# ledstripes.net
KiCad netlist of a schematic drawn in Altium Designer
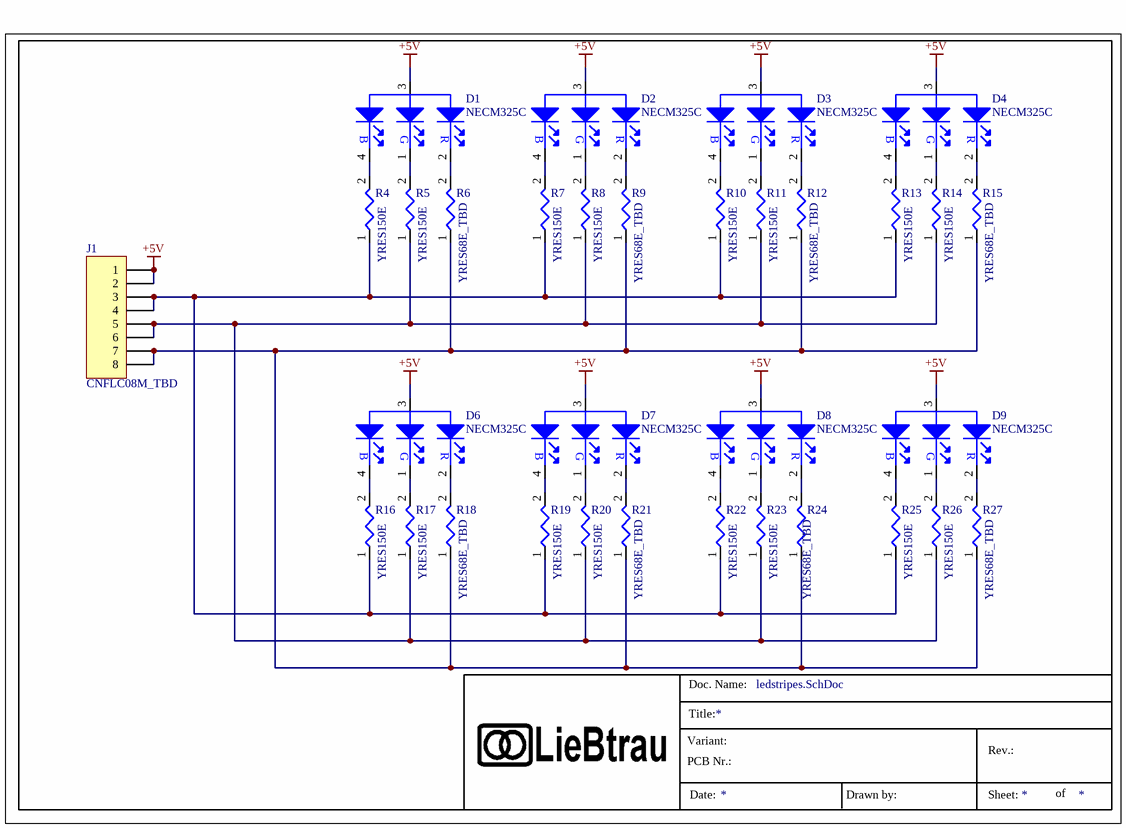
[diagram p0: ledstripes.SchDoc]

(export (version "E")
  (design (tool "Eeschema 10.0.6"))
  (components
    (comp (ref "D1")
      (value "NECM325C")
      (footprint "D_NECM325C")
      (libsource (lib "Testing") (part "D_LED_RGB"))
    )
    (comp (ref "D2")
      (value "NECM325C")
      (footprint "D_NECM325C")
      (libsource (lib "Testing") (part "D_LED_RGB"))
    )
    (comp (ref "D3")
      (value "NECM325C")
      (footprint "D_NECM325C")
      (libsource (lib "Testing") (part "D_LED_RGB"))
    )
    (comp (ref "D4")
      (value "NECM325C")
      (footprint "D_NECM325C")
      (libsource (lib "Testing") (part "D_LED_RGB"))
    )
    (comp (ref "D6")
      (value "NECM325C")
      (footprint "D_NECM325C")
      (libsource (lib "Testing") (part "D_LED_RGB"))
    )
    (comp (ref "D7")
      (value "NECM325C")
      (footprint "D_NECM325C")
      (libsource (lib "Testing") (part "D_LED_RGB"))
    )
    (comp (ref "D8")
      (value "NECM325C")
      (footprint "D_NECM325C")
      (libsource (lib "Testing") (part "D_LED_RGB"))
    )
    (comp (ref "D9")
      (value "NECM325C")
      (footprint "D_NECM325C")
      (libsource (lib "Testing") (part "D_LED_RGB"))
    )
    (comp (ref "J1")
      (value "CNFLC08M_TBD")
      (footprint "J_215079-8")
      (fields (field (name "PART NUMBER") "CNFLC08F_TBD"))
      (libsource (lib "Testing") (part "J_8P"))
    )
    (comp (ref "R4")
      (value "YRES150E")
      (footprint "R_1206")
      (description "Resistor")
      (libsource (lib "Testing") (part "R_RES"))
    )
    (comp (ref "R5")
      (value "YRES150E")
      (footprint "R_1206")
      (description "Resistor")
      (libsource (lib "Testing") (part "R_RES"))
    )
    (comp (ref "R6")
      (value "YRES68E_TBD")
      (footprint "R_1206")
      (description "Resistor")
      (libsource (lib "Testing") (part "R_RES"))
    )
    (comp (ref "R7")
      (value "YRES150E")
      (footprint "R_1206")
      (description "Resistor")
      (libsource (lib "Testing") (part "R_RES"))
    )
    (comp (ref "R8")
      (value "YRES150E")
      (footprint "R_1206")
      (description "Resistor")
      (libsource (lib "Testing") (part "R_RES"))
    )
    (comp (ref "R9")
      (value "YRES68E_TBD")
      (footprint "R_1206")
      (description "Resistor")
      (libsource (lib "Testing") (part "R_RES"))
    )
    (comp (ref "R10")
      (value "YRES150E")
      (footprint "R_1206")
      (description "Resistor")
      (libsource (lib "Testing") (part "R_RES"))
    )
    (comp (ref "R11")
      (value "YRES150E")
      (footprint "R_1206")
      (description "Resistor")
      (libsource (lib "Testing") (part "R_RES"))
    )
    (comp (ref "R12")
      (value "YRES68E_TBD")
      (footprint "R_1206")
      (description "Resistor")
      (libsource (lib "Testing") (part "R_RES"))
    )
    (comp (ref "R13")
      (value "YRES150E")
      (footprint "R_1206")
      (description "Resistor")
      (libsource (lib "Testing") (part "R_RES"))
    )
    (comp (ref "R14")
      (value "YRES150E")
      (footprint "R_1206")
      (description "Resistor")
      (libsource (lib "Testing") (part "R_RES"))
    )
    (comp (ref "R15")
      (value "YRES68E_TBD")
      (footprint "R_1206")
      (description "Resistor")
      (libsource (lib "Testing") (part "R_RES"))
    )
    (comp (ref "R16")
      (value "YRES150E")
      (footprint "R_1206")
      (description "Resistor")
      (libsource (lib "Testing") (part "R_RES"))
    )
    (comp (ref "R17")
      (value "YRES150E")
      (footprint "R_1206")
      (description "Resistor")
      (libsource (lib "Testing") (part "R_RES"))
    )
    (comp (ref "R18")
      (value "YRES68E_TBD")
      (footprint "R_1206")
      (description "Resistor")
      (libsource (lib "Testing") (part "R_RES"))
    )
    (comp (ref "R19")
      (value "YRES150E")
      (footprint "R_1206")
      (description "Resistor")
      (libsource (lib "Testing") (part "R_RES"))
    )
    (comp (ref "R20")
      (value "YRES150E")
      (footprint "R_1206")
      (description "Resistor")
      (libsource (lib "Testing") (part "R_RES"))
    )
    (comp (ref "R21")
      (value "YRES68E_TBD")
      (footprint "R_1206")
      (description "Resistor")
      (libsource (lib "Testing") (part "R_RES"))
    )
    (comp (ref "R22")
      (value "YRES150E")
      (footprint "R_1206")
      (description "Resistor")
      (libsource (lib "Testing") (part "R_RES"))
    )
    (comp (ref "R23")
      (value "YRES150E")
      (footprint "R_1206")
      (description "Resistor")
      (libsource (lib "Testing") (part "R_RES"))
    )
    (comp (ref "R24")
      (value "YRES68E_TBD")
      (footprint "R_1206")
      (description "Resistor")
      (libsource (lib "Testing") (part "R_RES"))
    )
    (comp (ref "R25")
      (value "YRES150E")
      (footprint "R_1206")
      (description "Resistor")
      (libsource (lib "Testing") (part "R_RES"))
    )
    (comp (ref "R26")
      (value "YRES150E")
      (footprint "R_1206")
      (description "Resistor")
      (libsource (lib "Testing") (part "R_RES"))
    )
    (comp (ref "R27")
      (value "YRES68E_TBD")
      (footprint "R_1206")
      (description "Resistor")
      (libsource (lib "Testing") (part "R_RES"))
    )
  )
  (nets
    (net (code "1") (name "+5V") (class "Default")
      (node (ref "D1") (pin "3") (pinfunction "A_3") (pintype "passive"))
      (node (ref "D2") (pin "3") (pinfunction "A_3") (pintype "passive"))
      (node (ref "D3") (pin "3") (pinfunction "A_3") (pintype "passive"))
      (node (ref "D4") (pin "3") (pinfunction "A_3") (pintype "passive"))
      (node (ref "D6") (pin "3") (pinfunction "A_3") (pintype "passive"))
      (node (ref "D7") (pin "3") (pinfunction "A_3") (pintype "passive"))
      (node (ref "D8") (pin "3") (pinfunction "A_3") (pintype "passive"))
      (node (ref "D9") (pin "3") (pinfunction "A_3") (pintype "passive"))
      (node (ref "J1") (pin "1") (pinfunction "1_1") (pintype "passive"))
      (node (ref "J1") (pin "2") (pinfunction "2_2") (pintype "passive"))
    )
    (net (code "2") (name "Net-(D1-C-Pad1)") (class "Default")
      (node (ref "D1") (pin "1") (pinfunction "C_1") (pintype "passive"))
      (node (ref "R5") (pin "2") (pinfunction "2_2") (pintype "passive"))
    )
    (net (code "3") (name "Net-(D1-C-Pad2)") (class "Default")
      (node (ref "D1") (pin "2") (pinfunction "C_2") (pintype "passive"))
      (node (ref "R6") (pin "2") (pinfunction "2_2") (pintype "passive"))
    )
    (net (code "4") (name "Net-(D1-C-Pad4)") (class "Default")
      (node (ref "D1") (pin "4") (pinfunction "C_4") (pintype "passive"))
      (node (ref "R4") (pin "2") (pinfunction "2_2") (pintype "passive"))
    )
    (net (code "5") (name "Net-(D2-C-Pad1)") (class "Default")
      (node (ref "D2") (pin "1") (pinfunction "C_1") (pintype "passive"))
      (node (ref "R8") (pin "2") (pinfunction "2_2") (pintype "passive"))
    )
    (net (code "6") (name "Net-(D2-C-Pad2)") (class "Default")
      (node (ref "D2") (pin "2") (pinfunction "C_2") (pintype "passive"))
      (node (ref "R9") (pin "2") (pinfunction "2_2") (pintype "passive"))
    )
    (net (code "7") (name "Net-(D2-C-Pad4)") (class "Default")
      (node (ref "D2") (pin "4") (pinfunction "C_4") (pintype "passive"))
      (node (ref "R7") (pin "2") (pinfunction "2_2") (pintype "passive"))
    )
    (net (code "8") (name "Net-(D3-C-Pad1)") (class "Default")
      (node (ref "D3") (pin "1") (pinfunction "C_1") (pintype "passive"))
      (node (ref "R11") (pin "2") (pinfunction "2_2") (pintype "passive"))
    )
    (net (code "9") (name "Net-(D3-C-Pad2)") (class "Default")
      (node (ref "D3") (pin "2") (pinfunction "C_2") (pintype "passive"))
      (node (ref "R12") (pin "2") (pinfunction "2_2") (pintype "passive"))
    )
    (net (code "10") (name "Net-(D3-C-Pad4)") (class "Default")
      (node (ref "D3") (pin "4") (pinfunction "C_4") (pintype "passive"))
      (node (ref "R10") (pin "2") (pinfunction "2_2") (pintype "passive"))
    )
    (net (code "11") (name "Net-(D4-C-Pad1)") (class "Default")
      (node (ref "D4") (pin "1") (pinfunction "C_1") (pintype "passive"))
      (node (ref "R14") (pin "2") (pinfunction "2_2") (pintype "passive"))
    )
    (net (code "12") (name "Net-(D4-C-Pad2)") (class "Default")
      (node (ref "D4") (pin "2") (pinfunction "C_2") (pintype "passive"))
      (node (ref "R15") (pin "2") (pinfunction "2_2") (pintype "passive"))
    )
    (net (code "13") (name "Net-(D4-C-Pad4)") (class "Default")
      (node (ref "D4") (pin "4") (pinfunction "C_4") (pintype "passive"))
      (node (ref "R13") (pin "2") (pinfunction "2_2") (pintype "passive"))
    )
    (net (code "14") (name "Net-(D6-C-Pad1)") (class "Default")
      (node (ref "D6") (pin "1") (pinfunction "C_1") (pintype "passive"))
      (node (ref "R17") (pin "2") (pinfunction "2_2") (pintype "passive"))
    )
    (net (code "15") (name "Net-(D6-C-Pad2)") (class "Default")
      (node (ref "D6") (pin "2") (pinfunction "C_2") (pintype "passive"))
      (node (ref "R18") (pin "2") (pinfunction "2_2") (pintype "passive"))
    )
    (net (code "16") (name "Net-(D6-C-Pad4)") (class "Default")
      (node (ref "D6") (pin "4") (pinfunction "C_4") (pintype "passive"))
      (node (ref "R16") (pin "2") (pinfunction "2_2") (pintype "passive"))
    )
    (net (code "17") (name "Net-(D7-C-Pad1)") (class "Default")
      (node (ref "D7") (pin "1") (pinfunction "C_1") (pintype "passive"))
      (node (ref "R20") (pin "2") (pinfunction "2_2") (pintype "passive"))
    )
    (net (code "18") (name "Net-(D7-C-Pad2)") (class "Default")
      (node (ref "D7") (pin "2") (pinfunction "C_2") (pintype "passive"))
      (node (ref "R21") (pin "2") (pinfunction "2_2") (pintype "passive"))
    )
    (net (code "19") (name "Net-(D7-C-Pad4)") (class "Default")
      (node (ref "D7") (pin "4") (pinfunction "C_4") (pintype "passive"))
      (node (ref "R19") (pin "2") (pinfunction "2_2") (pintype "passive"))
    )
    (net (code "20") (name "Net-(D8-C-Pad1)") (class "Default")
      (node (ref "D8") (pin "1") (pinfunction "C_1") (pintype "passive"))
      (node (ref "R23") (pin "2") (pinfunction "2_2") (pintype "passive"))
    )
    (net (code "21") (name "Net-(D8-C-Pad2)") (class "Default")
      (node (ref "D8") (pin "2") (pinfunction "C_2") (pintype "passive"))
      (node (ref "R24") (pin "2") (pinfunction "2_2") (pintype "passive"))
    )
    (net (code "22") (name "Net-(D8-C-Pad4)") (class "Default")
      (node (ref "D8") (pin "4") (pinfunction "C_4") (pintype "passive"))
      (node (ref "R22") (pin "2") (pinfunction "2_2") (pintype "passive"))
    )
    (net (code "23") (name "Net-(D9-C-Pad1)") (class "Default")
      (node (ref "D9") (pin "1") (pinfunction "C_1") (pintype "passive"))
      (node (ref "R26") (pin "2") (pinfunction "2_2") (pintype "passive"))
    )
    (net (code "24") (name "Net-(D9-C-Pad2)") (class "Default")
      (node (ref "D9") (pin "2") (pinfunction "C_2") (pintype "passive"))
      (node (ref "R27") (pin "2") (pinfunction "2_2") (pintype "passive"))
    )
    (net (code "25") (name "Net-(D9-C-Pad4)") (class "Default")
      (node (ref "D9") (pin "4") (pinfunction "C_4") (pintype "passive"))
      (node (ref "R25") (pin "2") (pinfunction "2_2") (pintype "passive"))
    )
    (net (code "26") (name "Net-(J1-Pad3)") (class "Default")
      (node (ref "J1") (pin "3") (pinfunction "3_3") (pintype "passive"))
      (node (ref "J1") (pin "4") (pinfunction "4_4") (pintype "passive"))
      (node (ref "R10") (pin "1") (pinfunction "1_1") (pintype "passive"))
      (node (ref "R13") (pin "1") (pinfunction "1_1") (pintype "passive"))
      (node (ref "R16") (pin "1") (pinfunction "1_1") (pintype "passive"))
      (node (ref "R19") (pin "1") (pinfunction "1_1") (pintype "passive"))
      (node (ref "R22") (pin "1") (pinfunction "1_1") (pintype "passive"))
      (node (ref "R25") (pin "1") (pinfunction "1_1") (pintype "passive"))
      (node (ref "R4") (pin "1") (pinfunction "1_1") (pintype "passive"))
      (node (ref "R7") (pin "1") (pinfunction "1_1") (pintype "passive"))
    )
    (net (code "27") (name "Net-(J1-Pad5)") (class "Default")
      (node (ref "J1") (pin "5") (pinfunction "5_5") (pintype "passive"))
      (node (ref "J1") (pin "6") (pinfunction "6_6") (pintype "passive"))
      (node (ref "R11") (pin "1") (pinfunction "1_1") (pintype "passive"))
      (node (ref "R14") (pin "1") (pinfunction "1_1") (pintype "passive"))
      (node (ref "R17") (pin "1") (pinfunction "1_1") (pintype "passive"))
      (node (ref "R20") (pin "1") (pinfunction "1_1") (pintype "passive"))
      (node (ref "R23") (pin "1") (pinfunction "1_1") (pintype "passive"))
      (node (ref "R26") (pin "1") (pinfunction "1_1") (pintype "passive"))
      (node (ref "R5") (pin "1") (pinfunction "1_1") (pintype "passive"))
      (node (ref "R8") (pin "1") (pinfunction "1_1") (pintype "passive"))
    )
    (net (code "28") (name "Net-(J1-Pad7)") (class "Default")
      (node (ref "J1") (pin "7") (pinfunction "7_7") (pintype "passive"))
      (node (ref "J1") (pin "8") (pinfunction "8_8") (pintype "passive"))
      (node (ref "R12") (pin "1") (pinfunction "1_1") (pintype "passive"))
      (node (ref "R15") (pin "1") (pinfunction "1_1") (pintype "passive"))
      (node (ref "R18") (pin "1") (pinfunction "1_1") (pintype "passive"))
      (node (ref "R21") (pin "1") (pinfunction "1_1") (pintype "passive"))
      (node (ref "R24") (pin "1") (pinfunction "1_1") (pintype "passive"))
      (node (ref "R27") (pin "1") (pinfunction "1_1") (pintype "passive"))
      (node (ref "R6") (pin "1") (pinfunction "1_1") (pintype "passive"))
      (node (ref "R9") (pin "1") (pinfunction "1_1") (pintype "passive"))
    )
  )
)
